# beacon_board.net
KiCad netlist of a schematic drawn in EAGLE
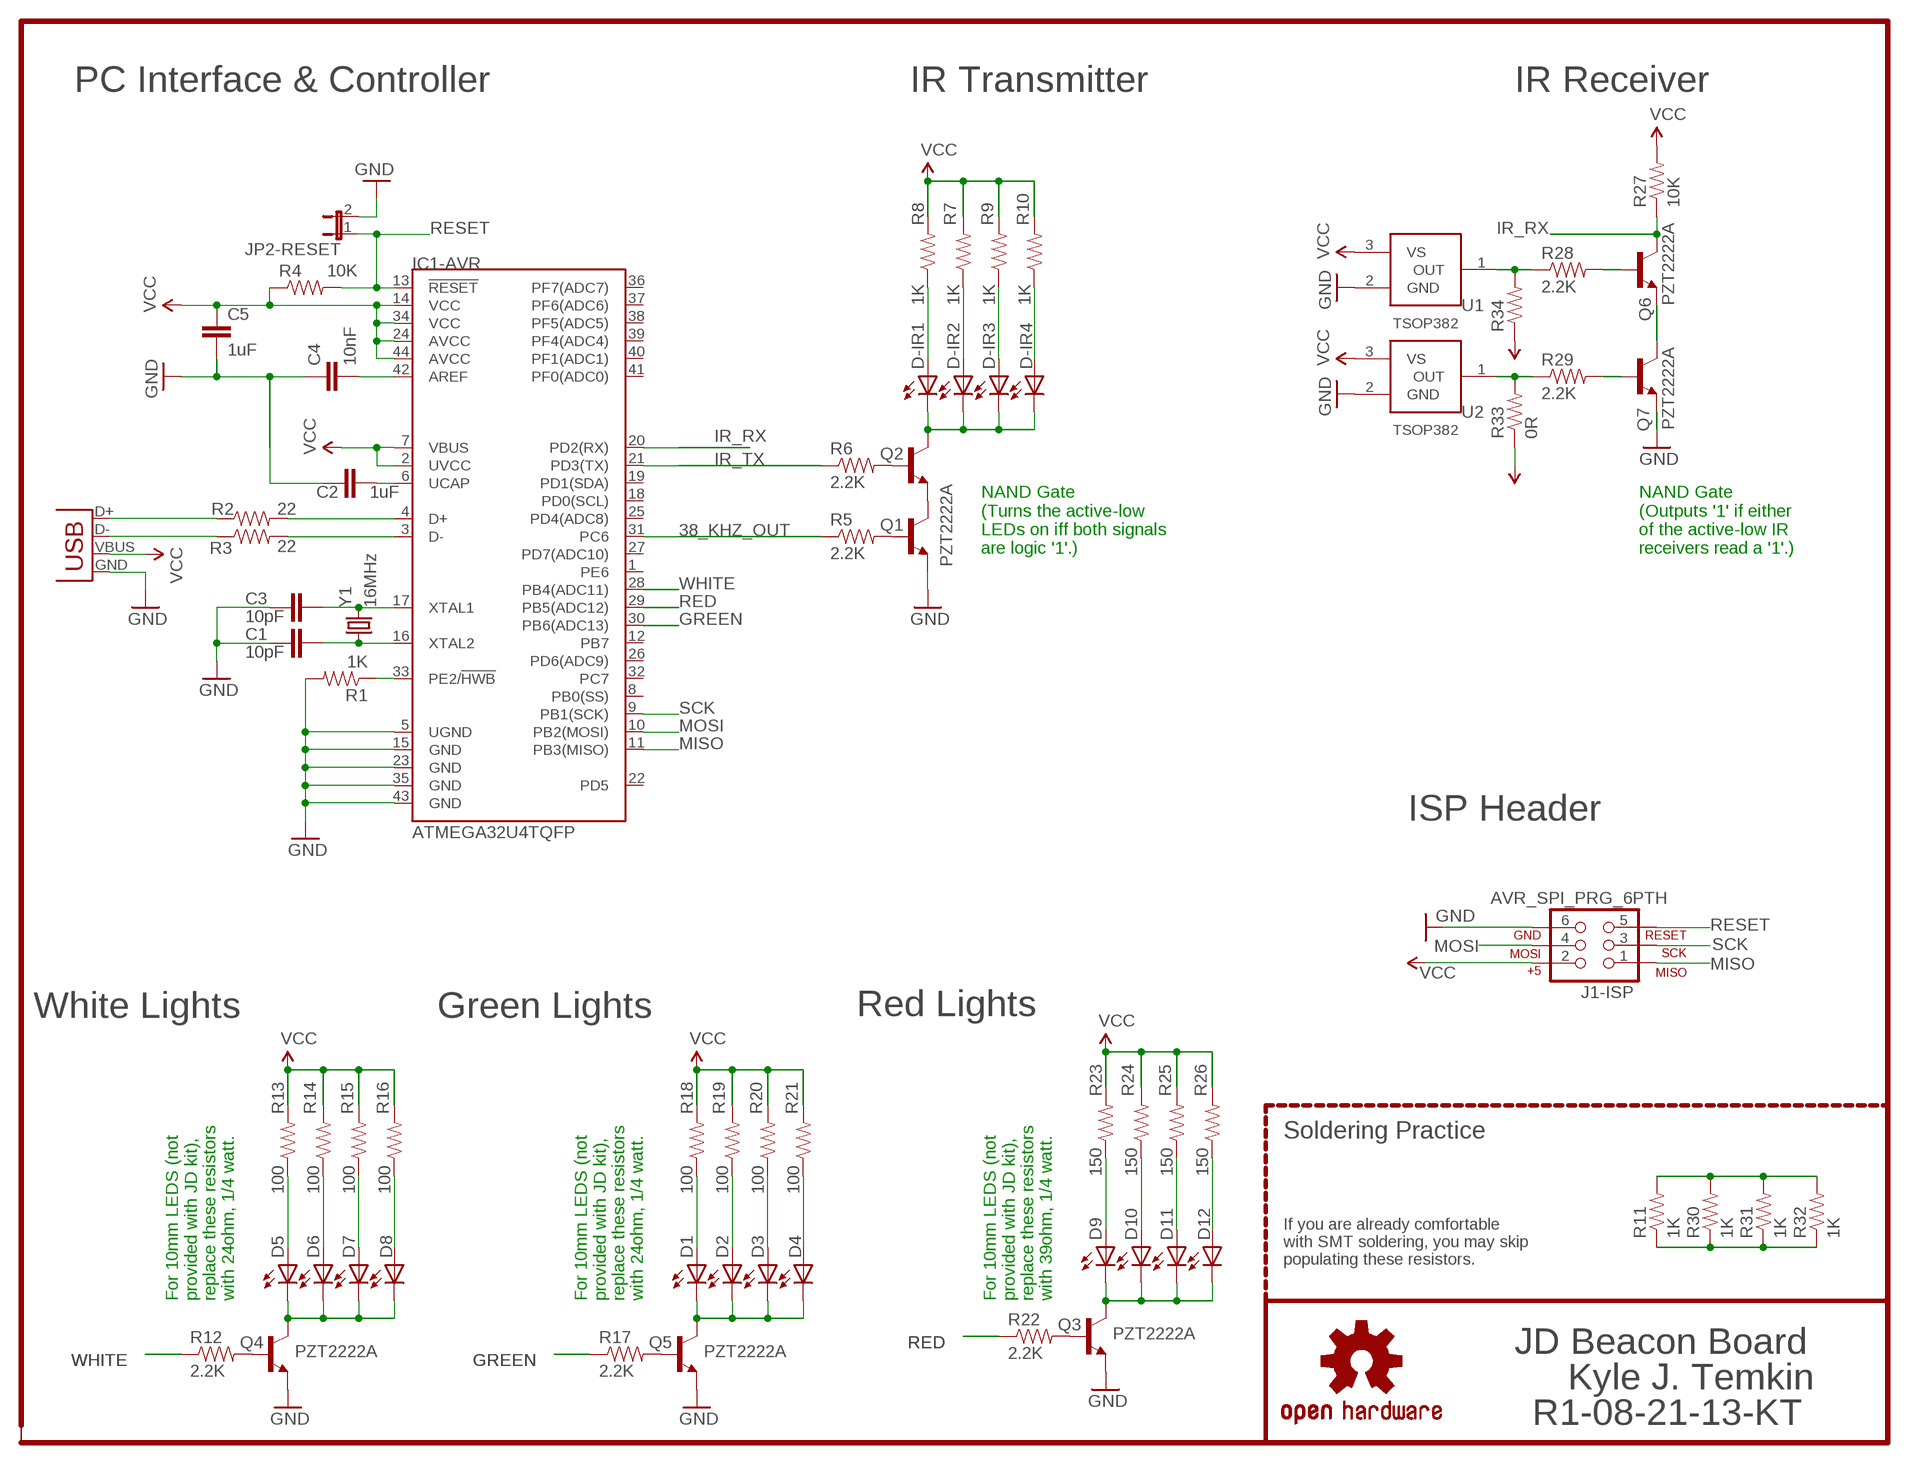
[diagram p0: schematic, sheet 1]

(export (version "E")
  (design (tool "Eeschema 10.0.6"))
  (components
    (comp (ref "C1")
      (value "10pF")
      (footprint "eagle-import:0805")
      (libsource (lib "eagle-import") (part "CAP0805"))
    )
    (comp (ref "C2")
      (value "1uF")
      (footprint "eagle-import:0805")
      (libsource (lib "eagle-import") (part "CAP0805"))
    )
    (comp (ref "C3")
      (value "10pF")
      (footprint "eagle-import:0805")
      (libsource (lib "eagle-import") (part "CAP0805"))
    )
    (comp (ref "C4")
      (value "10nF")
      (footprint "eagle-import:0805")
      (libsource (lib "eagle-import") (part "CAP0805"))
    )
    (comp (ref "C5")
      (value "1uF")
      (footprint "eagle-import:0805")
      (libsource (lib "eagle-import") (part "SparkFun-Passives_CAP0805"))
    )
    (comp (ref "D-IR1")
      (value "LED5MM")
      (footprint "eagle-import:LED5MM")
      (libsource (lib "eagle-import") (part "LED5MM"))
    )
    (comp (ref "D-IR2")
      (value "LED5MM")
      (footprint "eagle-import:LED5MM")
      (libsource (lib "eagle-import") (part "LED5MM"))
    )
    (comp (ref "D-IR3")
      (value "LED5MM")
      (footprint "eagle-import:LED5MM")
      (libsource (lib "eagle-import") (part "LED5MM"))
    )
    (comp (ref "D-IR4")
      (value "LED5MM")
      (footprint "eagle-import:LED5MM")
      (libsource (lib "eagle-import") (part "LED5MM"))
    )
    (comp (ref "D1")
      (value "LED10MM")
      (footprint "eagle-import:LED10MM")
      (libsource (lib "eagle-import") (part "beacon_board_LED10MM"))
    )
    (comp (ref "D2")
      (value "LED10MM")
      (footprint "eagle-import:LED10MM")
      (libsource (lib "eagle-import") (part "beacon_board_LED10MM"))
    )
    (comp (ref "D3")
      (value "LED10MM")
      (footprint "eagle-import:LED10MM")
      (libsource (lib "eagle-import") (part "beacon_board_LED10MM"))
    )
    (comp (ref "D4")
      (value "LED10MM")
      (footprint "eagle-import:LED10MM")
      (libsource (lib "eagle-import") (part "beacon_board_LED10MM"))
    )
    (comp (ref "D5")
      (value "LED10MM")
      (footprint "eagle-import:LED10MM")
      (libsource (lib "eagle-import") (part "beacon_board_LED10MM"))
    )
    (comp (ref "D6")
      (value "LED10MM")
      (footprint "eagle-import:LED10MM")
      (libsource (lib "eagle-import") (part "beacon_board_LED10MM"))
    )
    (comp (ref "D7")
      (value "LED10MM")
      (footprint "eagle-import:LED10MM")
      (libsource (lib "eagle-import") (part "beacon_board_LED10MM"))
    )
    (comp (ref "D8")
      (value "LED10MM")
      (footprint "eagle-import:LED10MM")
      (libsource (lib "eagle-import") (part "beacon_board_LED10MM"))
    )
    (comp (ref "D9")
      (value "LED10MM")
      (footprint "eagle-import:LED10MM")
      (libsource (lib "eagle-import") (part "beacon_board_LED10MM"))
    )
    (comp (ref "D10")
      (value "LED10MM")
      (footprint "eagle-import:LED10MM")
      (libsource (lib "eagle-import") (part "beacon_board_LED10MM"))
    )
    (comp (ref "D11")
      (value "LED10MM")
      (footprint "eagle-import:LED10MM")
      (libsource (lib "eagle-import") (part "beacon_board_LED10MM"))
    )
    (comp (ref "D12")
      (value "LED10MM")
      (footprint "eagle-import:LED10MM")
      (libsource (lib "eagle-import") (part "beacon_board_LED10MM"))
    )
    (comp (ref "IC1-AVR")
      (value "ATMEGA32U4TQFP")
      (footprint "eagle-import:SPARKFUN-DIGITALIC_TQFP44")
      (libsource (lib "eagle-import") (part "ATMEGA32U4TQFP"))
    )
    (comp (ref "J1-ISP")
      (value "AVR_SPI_PRG_6PTH")
      (footprint "eagle-import:2X3")
      (libsource (lib "eagle-import") (part "AVR_SPI_PRG_6PTH"))
    )
    (comp (ref "JP1")
      (value "USBSMD")
      (footprint "eagle-import:USB-MINIB")
      (libsource (lib "eagle-import") (part "USBSMD"))
    )
    (comp (ref "JP2-RESET")
      (value "JUMPER-2SMD-NO")
      (footprint "eagle-import:SJ_2S-NO")
      (libsource (lib "eagle-import") (part "JUMPER-2SMD-NO"))
    )
    (comp (ref "LOGO1")
      (value "OSHW-LOGOM")
      (footprint "eagle-import:OSHW-LOGO-M")
      (libsource (lib "eagle-import") (part "OSHW-LOGOM"))
    )
    (comp (ref "Q1")
      (value "PZT2222A")
      (footprint "eagle-import:SOT223")
      (libsource (lib "eagle-import") (part "PZT2222A"))
    )
    (comp (ref "Q2")
      (value "PZT2222A")
      (footprint "eagle-import:SOT223")
      (libsource (lib "eagle-import") (part "PZT2222A"))
    )
    (comp (ref "Q3")
      (value "PZT2222A")
      (footprint "eagle-import:SOT223")
      (libsource (lib "eagle-import") (part "PZT2222A"))
    )
    (comp (ref "Q4")
      (value "PZT2222A")
      (footprint "eagle-import:SOT223")
      (libsource (lib "eagle-import") (part "PZT2222A"))
    )
    (comp (ref "Q5")
      (value "PZT2222A")
      (footprint "eagle-import:SOT223")
      (libsource (lib "eagle-import") (part "PZT2222A"))
    )
    (comp (ref "Q6")
      (value "PZT2222A")
      (footprint "eagle-import:SOT223")
      (libsource (lib "eagle-import") (part "PZT2222A"))
    )
    (comp (ref "Q7")
      (value "PZT2222A")
      (footprint "eagle-import:SOT223")
      (libsource (lib "eagle-import") (part "PZT2222A"))
    )
    (comp (ref "R1")
      (value "1K")
      (footprint "eagle-import:0805")
      (libsource (lib "eagle-import") (part "RESISTOR0805-RES"))
    )
    (comp (ref "R2")
      (value "22")
      (footprint "eagle-import:0805")
      (libsource (lib "eagle-import") (part "SparkFun-Resistors_RESISTOR0805-RES"))
    )
    (comp (ref "R3")
      (value "22")
      (footprint "eagle-import:0805")
      (libsource (lib "eagle-import") (part "SparkFun-Resistors_RESISTOR0805-RES"))
    )
    (comp (ref "R4")
      (value "10K")
      (footprint "eagle-import:0805")
      (libsource (lib "eagle-import") (part "RESISTOR0805-RES"))
    )
    (comp (ref "R5")
      (value "2.2K")
      (footprint "eagle-import:0805")
      (libsource (lib "eagle-import") (part "SparkFun-Resistors_RESISTOR0805-RES"))
    )
    (comp (ref "R6")
      (value "2.2K")
      (footprint "eagle-import:0805")
      (libsource (lib "eagle-import") (part "SparkFun-Resistors_RESISTOR0805-RES"))
    )
    (comp (ref "R7")
      (value "1K")
      (footprint "eagle-import:0805")
      (libsource (lib "eagle-import") (part "SparkFun-Resistors_RESISTOR0805-RES"))
    )
    (comp (ref "R8")
      (value "1K")
      (footprint "eagle-import:0805")
      (libsource (lib "eagle-import") (part "SparkFun-Resistors_RESISTOR0805-RES"))
    )
    (comp (ref "R9")
      (value "1K")
      (footprint "eagle-import:0805")
      (libsource (lib "eagle-import") (part "SparkFun-Resistors_RESISTOR0805-RES"))
    )
    (comp (ref "R10")
      (value "1K")
      (footprint "eagle-import:0805")
      (libsource (lib "eagle-import") (part "SparkFun-Resistors_RESISTOR0805-RES"))
    )
    (comp (ref "R11")
      (value "1K")
      (footprint "eagle-import:0805")
      (libsource (lib "eagle-import") (part "RESISTOR0805-RES"))
    )
    (comp (ref "R12")
      (value "2.2K")
      (footprint "eagle-import:0805")
      (libsource (lib "eagle-import") (part "SparkFun-Resistors_RESISTOR0805-RES"))
    )
    (comp (ref "R13")
      (value "100")
      (footprint "eagle-import:0805")
      (libsource (lib "eagle-import") (part "SparkFun-Resistors_RESISTOR0805-RES"))
    )
    (comp (ref "R14")
      (value "100")
      (footprint "eagle-import:0805")
      (libsource (lib "eagle-import") (part "SparkFun-Resistors_RESISTOR0805-RES"))
    )
    (comp (ref "R15")
      (value "100")
      (footprint "eagle-import:0805")
      (libsource (lib "eagle-import") (part "SparkFun-Resistors_RESISTOR0805-RES"))
    )
    (comp (ref "R16")
      (value "100")
      (footprint "eagle-import:0805")
      (libsource (lib "eagle-import") (part "SparkFun-Resistors_RESISTOR0805-RES"))
    )
    (comp (ref "R17")
      (value "2.2K")
      (footprint "eagle-import:0805")
      (libsource (lib "eagle-import") (part "SparkFun-Resistors_RESISTOR0805-RES"))
    )
    (comp (ref "R18")
      (value "100")
      (footprint "eagle-import:0805")
      (libsource (lib "eagle-import") (part "SparkFun-Resistors_RESISTOR0805-RES"))
    )
    (comp (ref "R19")
      (value "100")
      (footprint "eagle-import:0805")
      (libsource (lib "eagle-import") (part "SparkFun-Resistors_RESISTOR0805-RES"))
    )
    (comp (ref "R20")
      (value "100")
      (footprint "eagle-import:0805")
      (libsource (lib "eagle-import") (part "SparkFun-Resistors_RESISTOR0805-RES"))
    )
    (comp (ref "R21")
      (value "100")
      (footprint "eagle-import:0805")
      (libsource (lib "eagle-import") (part "SparkFun-Resistors_RESISTOR0805-RES"))
    )
    (comp (ref "R22")
      (value "2.2K")
      (footprint "eagle-import:0805")
      (libsource (lib "eagle-import") (part "SparkFun-Resistors_RESISTOR0805-RES"))
    )
    (comp (ref "R23")
      (value "150")
      (footprint "eagle-import:0805")
      (libsource (lib "eagle-import") (part "SparkFun-Resistors_RESISTOR0805-RES"))
    )
    (comp (ref "R24")
      (value "150")
      (footprint "eagle-import:0805")
      (libsource (lib "eagle-import") (part "SparkFun-Resistors_RESISTOR0805-RES"))
    )
    (comp (ref "R25")
      (value "150")
      (footprint "eagle-import:0805")
      (libsource (lib "eagle-import") (part "SparkFun-Resistors_RESISTOR0805-RES"))
    )
    (comp (ref "R26")
      (value "150")
      (footprint "eagle-import:0805")
      (libsource (lib "eagle-import") (part "SparkFun-Resistors_RESISTOR0805-RES"))
    )
    (comp (ref "R27")
      (value "10K")
      (footprint "eagle-import:0805")
      (libsource (lib "eagle-import") (part "SparkFun-Resistors_RESISTOR0805-RES"))
    )
    (comp (ref "R28")
      (value "2.2K")
      (footprint "eagle-import:0805")
      (libsource (lib "eagle-import") (part "SparkFun-Resistors_RESISTOR0805-RES"))
    )
    (comp (ref "R29")
      (value "2.2K")
      (footprint "eagle-import:0805")
      (libsource (lib "eagle-import") (part "SparkFun-Resistors_RESISTOR0805-RES"))
    )
    (comp (ref "R30")
      (value "1K")
      (footprint "eagle-import:0805")
      (libsource (lib "eagle-import") (part "RESISTOR0805-RES"))
    )
    (comp (ref "R31")
      (value "1K")
      (footprint "eagle-import:0805")
      (libsource (lib "eagle-import") (part "RESISTOR0805-RES"))
    )
    (comp (ref "R32")
      (value "1K")
      (footprint "eagle-import:0805")
      (libsource (lib "eagle-import") (part "RESISTOR0805-RES"))
    )
    (comp (ref "R33")
      (value "0R")
      (footprint "eagle-import:0805")
      (libsource (lib "eagle-import") (part "SparkFun-Resistors_RESISTOR0805-RES"))
    )
    (comp (ref "R34")
      (value "RESISTOR0805-RES")
      (footprint "eagle-import:0805")
      (libsource (lib "eagle-import") (part "SparkFun-Resistors_RESISTOR0805-RES"))
    )
    (comp (ref "U$1")
      (value "BINGHAMTON-EECE-TEXT")
      (footprint "eagle-import:BINGHAMTON-EECE-TEXT")
      (libsource (lib "eagle-import") (part "BINGHAMTON-EECE-TEXT"))
    )
    (comp (ref "U1")
      (value "TSOP382")
      (footprint "eagle-import:TSOP382")
      (libsource (lib "eagle-import") (part "TSOP382"))
    )
    (comp (ref "U2")
      (value "TSOP382")
      (footprint "eagle-import:TSOP382")
      (libsource (lib "eagle-import") (part "TSOP382"))
    )
    (comp (ref "Y1")
      (value "16MHz")
      (footprint "eagle-import:HC49US")
      (libsource (lib "eagle-import") (part "CRYSTALHC49US"))
    )
  )
  (nets
    (net (code "1") (name "/38_KHZ_OUT") (class "Default")
      (node (ref "IC1-AVR") (pin "31") (pinfunction "PC6_31") (pintype "bidirectional"))
      (node (ref "R5") (pin "1") (pinfunction "1_1") (pintype "passive"))
    )
    (net (code "2") (name "/GREEN") (class "Default")
      (node (ref "IC1-AVR") (pin "30") (pinfunction "PB6(ADC13)_30") (pintype "bidirectional"))
      (node (ref "R17") (pin "1") (pinfunction "1_1") (pintype "passive"))
    )
    (net (code "3") (name "/IR_RX") (class "Default")
      (node (ref "IC1-AVR") (pin "20") (pinfunction "PD2(RX)_20") (pintype "bidirectional"))
      (node (ref "Q6") (pin "2") (pinfunction "C_2") (pintype "passive"))
      (node (ref "Q6") (pin "4") (pinfunction "C_4") (pintype "passive"))
      (node (ref "R27") (pin "1") (pinfunction "1_1") (pintype "passive"))
    )
    (net (code "4") (name "/IR_TX") (class "Default")
      (node (ref "IC1-AVR") (pin "21") (pinfunction "PD3(TX)_21") (pintype "bidirectional"))
      (node (ref "R6") (pin "1") (pinfunction "1_1") (pintype "passive"))
    )
    (net (code "5") (name "/MISO") (class "Default")
      (node (ref "IC1-AVR") (pin "11") (pinfunction "PB3(MISO)_11") (pintype "bidirectional"))
      (node (ref "J1-ISP") (pin "1") (pinfunction "1_1") (pintype "passive"))
    )
    (net (code "6") (name "/MOSI") (class "Default")
      (node (ref "IC1-AVR") (pin "10") (pinfunction "PB2(MOSI)_10") (pintype "bidirectional"))
      (node (ref "J1-ISP") (pin "4") (pinfunction "4_4") (pintype "passive"))
    )
    (net (code "7") (name "/RED") (class "Default")
      (node (ref "IC1-AVR") (pin "29") (pinfunction "PB5(ADC12)_29") (pintype "bidirectional"))
      (node (ref "R22") (pin "1") (pinfunction "1_1") (pintype "passive"))
    )
    (net (code "8") (name "/RESET") (class "Default")
      (node (ref "IC1-AVR") (pin "13") (pinfunction "~{RESET}_13") (pintype "bidirectional"))
      (node (ref "J1-ISP") (pin "5") (pinfunction "5_5") (pintype "passive"))
      (node (ref "JP2-RESET") (pin "1") (pinfunction "1_1") (pintype "passive"))
      (node (ref "R4") (pin "2") (pinfunction "2_2") (pintype "passive"))
    )
    (net (code "9") (name "/SCK") (class "Default")
      (node (ref "IC1-AVR") (pin "9") (pinfunction "PB1(SCK)_9") (pintype "bidirectional"))
      (node (ref "J1-ISP") (pin "3") (pinfunction "3_3") (pintype "passive"))
    )
    (net (code "10") (name "/WHITE") (class "Default")
      (node (ref "IC1-AVR") (pin "28") (pinfunction "PB4(ADC11)_28") (pintype "bidirectional"))
      (node (ref "R12") (pin "1") (pinfunction "1_1") (pintype "passive"))
    )
    (net (code "11") (name "GND") (class "Default")
      (node (ref "C1") (pin "1") (pinfunction "1_1") (pintype "passive"))
      (node (ref "C2") (pin "1") (pinfunction "1_1") (pintype "passive"))
      (node (ref "C3") (pin "1") (pinfunction "1_1") (pintype "passive"))
      (node (ref "C4") (pin "1") (pinfunction "1_1") (pintype "passive"))
      (node (ref "C5") (pin "2") (pinfunction "2_2") (pintype "passive"))
      (node (ref "IC1-AVR") (pin "15") (pinfunction "GND_15") (pintype "bidirectional"))
      (node (ref "IC1-AVR") (pin "23") (pinfunction "GND_23") (pintype "bidirectional"))
      (node (ref "IC1-AVR") (pin "35") (pinfunction "GND_35") (pintype "bidirectional"))
      (node (ref "IC1-AVR") (pin "43") (pinfunction "GND_43") (pintype "bidirectional"))
      (node (ref "IC1-AVR") (pin "5") (pinfunction "UGND_5") (pintype "bidirectional"))
      (node (ref "J1-ISP") (pin "6") (pinfunction "6_6") (pintype "passive"))
      (node (ref "JP1") (pin "GND") (pinfunction "GND_GND") (pintype "bidirectional"))
      (node (ref "JP2-RESET") (pin "2") (pinfunction "2_2") (pintype "passive"))
      (node (ref "Q1") (pin "3") (pinfunction "E_3") (pintype "passive"))
      (node (ref "Q3") (pin "3") (pinfunction "E_3") (pintype "passive"))
      (node (ref "Q4") (pin "3") (pinfunction "E_3") (pintype "passive"))
      (node (ref "Q5") (pin "3") (pinfunction "E_3") (pintype "passive"))
      (node (ref "Q7") (pin "3") (pinfunction "E_3") (pintype "passive"))
      (node (ref "R1") (pin "2") (pinfunction "2_2") (pintype "passive"))
      (node (ref "U1") (pin "2") (pinfunction "GND_2") (pintype "bidirectional"))
      (node (ref "U2") (pin "2") (pinfunction "GND_2") (pintype "bidirectional"))
    )
    (net (code "12") (name "Net-(D-IR1-C)") (class "Default")
      (node (ref "D-IR1") (pin "K") (pinfunction "C_K") (pintype "passive"))
      (node (ref "D-IR2") (pin "K") (pinfunction "C_K") (pintype "passive"))
      (node (ref "D-IR3") (pin "K") (pinfunction "C_K") (pintype "passive"))
      (node (ref "D-IR4") (pin "K") (pinfunction "C_K") (pintype "passive"))
      (node (ref "Q2") (pin "2") (pinfunction "C_2") (pintype "passive"))
      (node (ref "Q2") (pin "4") (pinfunction "C_4") (pintype "passive"))
    )
    (net (code "13") (name "Net-(D-IR1-PadA)") (class "Default")
      (node (ref "D-IR1") (pin "A") (pinfunction "A_A") (pintype "passive"))
      (node (ref "R8") (pin "1") (pinfunction "1_1") (pintype "passive"))
    )
    (net (code "14") (name "Net-(D-IR2-PadA)") (class "Default")
      (node (ref "D-IR2") (pin "A") (pinfunction "A_A") (pintype "passive"))
      (node (ref "R7") (pin "1") (pinfunction "1_1") (pintype "passive"))
    )
    (net (code "15") (name "Net-(D-IR3-PadA)") (class "Default")
      (node (ref "D-IR3") (pin "A") (pinfunction "A_A") (pintype "passive"))
      (node (ref "R9") (pin "1") (pinfunction "1_1") (pintype "passive"))
    )
    (net (code "16") (name "Net-(D-IR4-PadA)") (class "Default")
      (node (ref "D-IR4") (pin "A") (pinfunction "A_A") (pintype "passive"))
      (node (ref "R10") (pin "1") (pinfunction "1_1") (pintype "passive"))
    )
    (net (code "17") (name "Net-(D1-PadA)") (class "Default")
      (node (ref "D1") (pin "A") (pinfunction "A_A") (pintype "passive"))
      (node (ref "R18") (pin "1") (pinfunction "1_1") (pintype "passive"))
    )
    (net (code "18") (name "Net-(D1-PadC)") (class "Default")
      (node (ref "D1") (pin "C") (pinfunction "C_C") (pintype "passive"))
      (node (ref "D2") (pin "C") (pinfunction "C_C") (pintype "passive"))
      (node (ref "D3") (pin "C") (pinfunction "C_C") (pintype "passive"))
      (node (ref "D4") (pin "C") (pinfunction "C_C") (pintype "passive"))
      (node (ref "Q5") (pin "2") (pinfunction "C_2") (pintype "passive"))
      (node (ref "Q5") (pin "4") (pinfunction "C_4") (pintype "passive"))
    )
    (net (code "19") (name "Net-(D2-PadA)") (class "Default")
      (node (ref "D2") (pin "A") (pinfunction "A_A") (pintype "passive"))
      (node (ref "R19") (pin "1") (pinfunction "1_1") (pintype "passive"))
    )
    (net (code "20") (name "Net-(D3-PadA)") (class "Default")
      (node (ref "D3") (pin "A") (pinfunction "A_A") (pintype "passive"))
      (node (ref "R20") (pin "1") (pinfunction "1_1") (pintype "passive"))
    )
    (net (code "21") (name "Net-(D4-PadA)") (class "Default")
      (node (ref "D4") (pin "A") (pinfunction "A_A") (pintype "passive"))
      (node (ref "R21") (pin "1") (pinfunction "1_1") (pintype "passive"))
    )
    (net (code "22") (name "Net-(D5-PadA)") (class "Default")
      (node (ref "D5") (pin "A") (pinfunction "A_A") (pintype "passive"))
      (node (ref "R13") (pin "1") (pinfunction "1_1") (pintype "passive"))
    )
    (net (code "23") (name "Net-(D5-PadC)") (class "Default")
      (node (ref "D5") (pin "C") (pinfunction "C_C") (pintype "passive"))
      (node (ref "D6") (pin "C") (pinfunction "C_C") (pintype "passive"))
      (node (ref "D7") (pin "C") (pinfunction "C_C") (pintype "passive"))
      (node (ref "D8") (pin "C") (pinfunction "C_C") (pintype "passive"))
      (node (ref "Q4") (pin "2") (pinfunction "C_2") (pintype "passive"))
      (node (ref "Q4") (pin "4") (pinfunction "C_4") (pintype "passive"))
    )
    (net (code "24") (name "Net-(D6-PadA)") (class "Default")
      (node (ref "D6") (pin "A") (pinfunction "A_A") (pintype "passive"))
      (node (ref "R14") (pin "1") (pinfunction "1_1") (pintype "passive"))
    )
    (net (code "25") (name "Net-(D7-PadA)") (class "Default")
      (node (ref "D7") (pin "A") (pinfunction "A_A") (pintype "passive"))
      (node (ref "R15") (pin "1") (pinfunction "1_1") (pintype "passive"))
    )
    (net (code "26") (name "Net-(D8-PadA)") (class "Default")
      (node (ref "D8") (pin "A") (pinfunction "A_A") (pintype "passive"))
      (node (ref "R16") (pin "1") (pinfunction "1_1") (pintype "passive"))
    )
    (net (code "27") (name "Net-(D9-PadA)") (class "Default")
      (node (ref "D9") (pin "A") (pinfunction "A_A") (pintype "passive"))
      (node (ref "R23") (pin "1") (pinfunction "1_1") (pintype "passive"))
    )
    (net (code "28") (name "Net-(D10-PadA)") (class "Default")
      (node (ref "D10") (pin "A") (pinfunction "A_A") (pintype "passive"))
      (node (ref "R24") (pin "1") (pinfunction "1_1") (pintype "passive"))
    )
    (net (code "29") (name "Net-(D10-PadC)") (class "Default")
      (node (ref "D10") (pin "C") (pinfunction "C_C") (pintype "passive"))
      (node (ref "D11") (pin "C") (pinfunction "C_C") (pintype "passive"))
      (node (ref "D12") (pin "C") (pinfunction "C_C") (pintype "passive"))
      (node (ref "D9") (pin "C") (pinfunction "C_C") (pintype "passive"))
      (node (ref "Q3") (pin "2") (pinfunction "C_2") (pintype "passive"))
      (node (ref "Q3") (pin "4") (pinfunction "C_4") (pintype "passive"))
    )
    (net (code "30") (name "Net-(D11-PadA)") (class "Default")
      (node (ref "D11") (pin "A") (pinfunction "A_A") (pintype "passive"))
      (node (ref "R25") (pin "1") (pinfunction "1_1") (pintype "passive"))
    )
    (net (code "31") (name "Net-(D12-PadA)") (class "Default")
      (node (ref "D12") (pin "A") (pinfunction "A_A") (pintype "passive"))
      (node (ref "R26") (pin "1") (pinfunction "1_1") (pintype "passive"))
    )
    (net (code "32") (name "Net-(IC1-AVR-AREF)") (class "Default")
      (node (ref "C4") (pin "2") (pinfunction "2_2") (pintype "passive"))
      (node (ref "IC1-AVR") (pin "42") (pinfunction "AREF_42") (pintype "bidirectional"))
    )
    (net (code "33") (name "Net-(IC1-AVR-D+)") (class "Default")
      (node (ref "IC1-AVR") (pin "4") (pinfunction "D+_4") (pintype "bidirectional"))
      (node (ref "R2") (pin "2") (pinfunction "2_2") (pintype "passive"))
    )
    (net (code "34") (name "Net-(IC1-AVR-D-)") (class "Default")
      (node (ref "IC1-AVR") (pin "3") (pinfunction "D-_3") (pintype "bidirectional"))
      (node (ref "R3") (pin "2") (pinfunction "2_2") (pintype "passive"))
    )
    (net (code "35") (name "Net-(IC1-AVR-PE2{slash}~{HWB})") (class "Default")
      (node (ref "IC1-AVR") (pin "33") (pinfunction "PE2/~{HWB}_33") (pintype "bidirectional"))
      (node (ref "R1") (pin "1") (pinfunction "1_1") (pintype "passive"))
    )
    (net (code "36") (name "Net-(IC1-AVR-UCAP)") (class "Default")
      (node (ref "C2") (pin "2") (pinfunction "2_2") (pintype "passive"))
      (node (ref "IC1-AVR") (pin "6") (pinfunction "UCAP_6") (pintype "bidirectional"))
    )
    (net (code "37") (name "Net-(IC1-AVR-XTAL1)") (class "Default")
      (node (ref "C3") (pin "2") (pinfunction "2_2") (pintype "passive"))
      (node (ref "IC1-AVR") (pin "17") (pinfunction "XTAL1_17") (pintype "bidirectional"))
      (node (ref "Y1") (pin "2") (pinfunction "2_2") (pintype "passive"))
    )
    (net (code "38") (name "Net-(IC1-AVR-XTAL2)") (class "Default")
      (node (ref "C1") (pin "2") (pinfunction "2_2") (pintype "passive"))
      (node (ref "IC1-AVR") (pin "16") (pinfunction "XTAL2_16") (pintype "bidirectional"))
      (node (ref "Y1") (pin "1") (pinfunction "1_1") (pintype "passive"))
    )
    (net (code "39") (name "Net-(JP1-PadD+)") (class "Default")
      (node (ref "JP1") (pin "D+") (pinfunction "D+_D+") (pintype "bidirectional"))
      (node (ref "R2") (pin "1") (pinfunction "1_1") (pintype "passive"))
    )
    (net (code "40") (name "Net-(JP1-PadD-)") (class "Default")
      (node (ref "JP1") (pin "D-") (pinfunction "D-_D-") (pintype "bidirectional"))
      (node (ref "R3") (pin "1") (pinfunction "1_1") (pintype "passive"))
    )
    (net (code "41") (name "Net-(Q1-B)") (class "Default")
      (node (ref "Q1") (pin "1") (pinfunction "B_1") (pintype "passive"))
      (node (ref "R5") (pin "2") (pinfunction "2_2") (pintype "passive"))
    )
    (net (code "42") (name "Net-(Q2-B)") (class "Default")
      (node (ref "Q2") (pin "1") (pinfunction "B_1") (pintype "passive"))
      (node (ref "R6") (pin "2") (pinfunction "2_2") (pintype "passive"))
    )
    (net (code "43") (name "Net-(Q2-E)") (class "Default")
      (node (ref "Q1") (pin "2") (pinfunction "C_2") (pintype "passive"))
      (node (ref "Q1") (pin "4") (pinfunction "C_4") (pintype "passive"))
      (node (ref "Q2") (pin "3") (pinfunction "E_3") (pintype "passive"))
    )
    (net (code "44") (name "Net-(Q3-B)") (class "Default")
      (node (ref "Q3") (pin "1") (pinfunction "B_1") (pintype "passive"))
      (node (ref "R22") (pin "2") (pinfunction "2_2") (pintype "passive"))
    )
    (net (code "45") (name "Net-(Q4-B)") (class "Default")
      (node (ref "Q4") (pin "1") (pinfunction "B_1") (pintype "passive"))
      (node (ref "R12") (pin "2") (pinfunction "2_2") (pintype "passive"))
    )
    (net (code "46") (name "Net-(Q5-B)") (class "Default")
      (node (ref "Q5") (pin "1") (pinfunction "B_1") (pintype "passive"))
      (node (ref "R17") (pin "2") (pinfunction "2_2") (pintype "passive"))
    )
    (net (code "47") (name "Net-(Q6-B)") (class "Default")
      (node (ref "Q6") (pin "1") (pinfunction "B_1") (pintype "passive"))
      (node (ref "R28") (pin "2") (pinfunction "2_2") (pintype "passive"))
    )
    (net (code "48") (name "Net-(Q6-E)") (class "Default")
      (node (ref "Q6") (pin "3") (pinfunction "E_3") (pintype "passive"))
      (node (ref "Q7") (pin "2") (pinfunction "C_2") (pintype "passive"))
      (node (ref "Q7") (pin "4") (pinfunction "C_4") (pintype "passive"))
    )
    (net (code "49") (name "Net-(Q7-B)") (class "Default")
      (node (ref "Q7") (pin "1") (pinfunction "B_1") (pintype "passive"))
      (node (ref "R29") (pin "2") (pinfunction "2_2") (pintype "passive"))
    )
    (net (code "50") (name "Net-(R11-Pad1)") (class "Default")
      (node (ref "R11") (pin "1") (pinfunction "1_1") (pintype "passive"))
      (node (ref "R30") (pin "1") (pinfunction "1_1") (pintype "passive"))
      (node (ref "R31") (pin "1") (pinfunction "1_1") (pintype "passive"))
      (node (ref "R32") (pin "1") (pinfunction "1_1") (pintype "passive"))
    )
    (net (code "51") (name "Net-(R11-Pad2)") (class "Default")
      (node (ref "R11") (pin "2") (pinfunction "2_2") (pintype "passive"))
      (node (ref "R30") (pin "2") (pinfunction "2_2") (pintype "passive"))
      (node (ref "R31") (pin "2") (pinfunction "2_2") (pintype "passive"))
      (node (ref "R32") (pin "2") (pinfunction "2_2") (pintype "passive"))
    )
    (net (code "52") (name "Net-(U1-OUT)") (class "Default")
      (node (ref "R28") (pin "1") (pinfunction "1_1") (pintype "passive"))
      (node (ref "R34") (pin "2") (pinfunction "2_2") (pintype "passive"))
      (node (ref "U1") (pin "1") (pinfunction "OUT_1") (pintype "bidirectional"))
    )
    (net (code "53") (name "Net-(U2-OUT)") (class "Default")
      (node (ref "R29") (pin "1") (pinfunction "1_1") (pintype "passive"))
      (node (ref "R33") (pin "2") (pinfunction "2_2") (pintype "passive"))
      (node (ref "U2") (pin "1") (pinfunction "OUT_1") (pintype "bidirectional"))
    )
    (net (code "54") (name "VCC") (class "Default")
      (node (ref "C5") (pin "1") (pinfunction "1_1") (pintype "passive"))
      (node (ref "IC1-AVR") (pin "14") (pinfunction "VCC_14") (pintype "bidirectional"))
      (node (ref "IC1-AVR") (pin "2") (pinfunction "UVCC_2") (pintype "bidirectional"))
      (node (ref "IC1-AVR") (pin "24") (pinfunction "AVCC_24") (pintype "bidirectional"))
      (node (ref "IC1-AVR") (pin "34") (pinfunction "VCC_34") (pintype "bidirectional"))
      (node (ref "IC1-AVR") (pin "44") (pinfunction "AVCC_44") (pintype "bidirectional"))
      (node (ref "IC1-AVR") (pin "7") (pinfunction "VBUS_7") (pintype "bidirectional"))
      (node (ref "J1-ISP") (pin "2") (pinfunction "2_2") (pintype "passive"))
      (node (ref "JP1") (pin "VBUS") (pinfunction "VBUS_VBUS") (pintype "bidirectional"))
      (node (ref "R10") (pin "2") (pinfunction "2_2") (pintype "passive"))
      (node (ref "R13") (pin "2") (pinfunction "2_2") (pintype "passive"))
      (node (ref "R14") (pin "2") (pinfunction "2_2") (pintype "passive"))
      (node (ref "R15") (pin "2") (pinfunction "2_2") (pintype "passive"))
      (node (ref "R16") (pin "2") (pinfunction "2_2") (pintype "passive"))
      (node (ref "R18") (pin "2") (pinfunction "2_2") (pintype "passive"))
      (node (ref "R19") (pin "2") (pinfunction "2_2") (pintype "passive"))
      (node (ref "R20") (pin "2") (pinfunction "2_2") (pintype "passive"))
      (node (ref "R21") (pin "2") (pinfunction "2_2") (pintype "passive"))
      (node (ref "R23") (pin "2") (pinfunction "2_2") (pintype "passive"))
      (node (ref "R24") (pin "2") (pinfunction "2_2") (pintype "passive"))
      (node (ref "R25") (pin "2") (pinfunction "2_2") (pintype "passive"))
      (node (ref "R26") (pin "2") (pinfunction "2_2") (pintype "passive"))
      (node (ref "R27") (pin "2") (pinfunction "2_2") (pintype "passive"))
      (node (ref "R33") (pin "1") (pinfunction "1_1") (pintype "passive"))
      (node (ref "R34") (pin "1") (pinfunction "1_1") (pintype "passive"))
      (node (ref "R4") (pin "1") (pinfunction "1_1") (pintype "passive"))
      (node (ref "R7") (pin "2") (pinfunction "2_2") (pintype "passive"))
      (node (ref "R8") (pin "2") (pinfunction "2_2") (pintype "passive"))
      (node (ref "R9") (pin "2") (pinfunction "2_2") (pintype "passive"))
      (node (ref "U1") (pin "3") (pinfunction "VS_3") (pintype "bidirectional"))
      (node (ref "U2") (pin "3") (pinfunction "VS_3") (pintype "bidirectional"))
    )
    (net (code "55") (name "unconnected-(IC1-AVR-PB0(SS)-Pad8)") (class "Default")
      (node (ref "IC1-AVR") (pin "8") (pinfunction "PB0(SS)_8") (pintype "bidirectional"))
    )
    (net (code "56") (name "unconnected-(IC1-AVR-PB7-Pad12)") (class "Default")
      (node (ref "IC1-AVR") (pin "12") (pinfunction "PB7_12") (pintype "bidirectional"))
    )
    (net (code "57") (name "unconnected-(IC1-AVR-PC7-Pad32)") (class "Default")
      (node (ref "IC1-AVR") (pin "32") (pinfunction "PC7_32") (pintype "bidirectional"))
    )
    (net (code "58") (name "unconnected-(IC1-AVR-PD0(SCL)-Pad18)") (class "Default")
      (node (ref "IC1-AVR") (pin "18") (pinfunction "PD0(SCL)_18") (pintype "bidirectional"))
    )
    (net (code "59") (name "unconnected-(IC1-AVR-PD1(SDA)-Pad19)") (class "Default")
      (node (ref "IC1-AVR") (pin "19") (pinfunction "PD1(SDA)_19") (pintype "bidirectional"))
    )
    (net (code "60") (name "unconnected-(IC1-AVR-PD4(ADC8)-Pad25)") (class "Default")
      (node (ref "IC1-AVR") (pin "25") (pinfunction "PD4(ADC8)_25") (pintype "bidirectional"))
    )
    (net (code "61") (name "unconnected-(IC1-AVR-PD5-Pad22)") (class "Default")
      (node (ref "IC1-AVR") (pin "22") (pinfunction "PD5_22") (pintype "bidirectional"))
    )
    (net (code "62") (name "unconnected-(IC1-AVR-PD6(ADC9)-Pad26)") (class "Default")
      (node (ref "IC1-AVR") (pin "26") (pinfunction "PD6(ADC9)_26") (pintype "bidirectional"))
    )
    (net (code "63") (name "unconnected-(IC1-AVR-PD7(ADC10)-Pad27)") (class "Default")
      (node (ref "IC1-AVR") (pin "27") (pinfunction "PD7(ADC10)_27") (pintype "bidirectional"))
    )
    (net (code "64") (name "unconnected-(IC1-AVR-PE6-Pad1)") (class "Default")
      (node (ref "IC1-AVR") (pin "1") (pinfunction "PE6_1") (pintype "bidirectional"))
    )
    (net (code "65") (name "unconnected-(IC1-AVR-PF0(ADC0)-Pad41)") (class "Default")
      (node (ref "IC1-AVR") (pin "41") (pinfunction "PF0(ADC0)_41") (pintype "bidirectional"))
    )
    (net (code "66") (name "unconnected-(IC1-AVR-PF1(ADC1)-Pad40)") (class "Default")
      (node (ref "IC1-AVR") (pin "40") (pinfunction "PF1(ADC1)_40") (pintype "bidirectional"))
    )
    (net (code "67") (name "unconnected-(IC1-AVR-PF4(ADC4)-Pad39)") (class "Default")
      (node (ref "IC1-AVR") (pin "39") (pinfunction "PF4(ADC4)_39") (pintype "bidirectional"))
    )
    (net (code "68") (name "unconnected-(IC1-AVR-PF5(ADC5)-Pad38)") (class "Default")
      (node (ref "IC1-AVR") (pin "38") (pinfunction "PF5(ADC5)_38") (pintype "bidirectional"))
    )
    (net (code "69") (name "unconnected-(IC1-AVR-PF6(ADC6)-Pad37)") (class "Default")
      (node (ref "IC1-AVR") (pin "37") (pinfunction "PF6(ADC6)_37") (pintype "bidirectional"))
    )
    (net (code "70") (name "unconnected-(IC1-AVR-PF7(ADC7)-Pad36)") (class "Default")
      (node (ref "IC1-AVR") (pin "36") (pinfunction "PF7(ADC7)_36") (pintype "bidirectional"))
    )
  )
)
